# dsub37_to_rj45.net
KiCad netlist of a schematic drawn in EAGLE
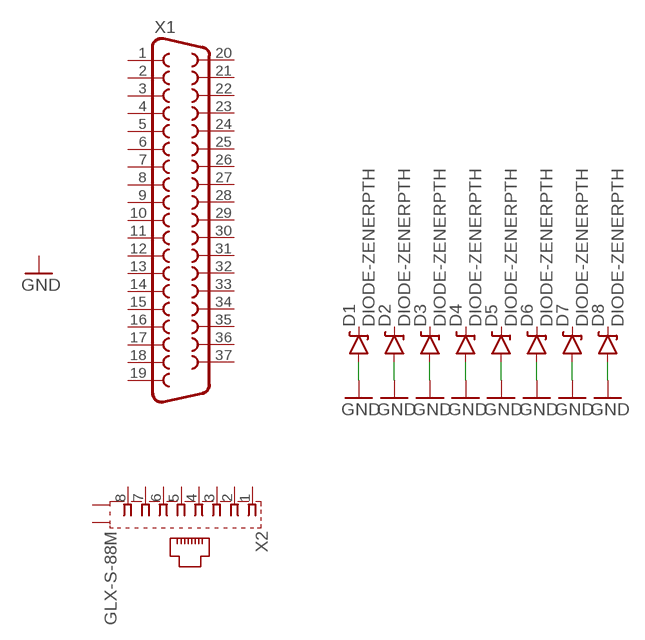
[diagram p0: schematic, sheet 1]

(export (version "E")
  (design (tool "Eeschema 10.0.6"))
  (components
    (comp (ref "D1")
      (value "DIODE-ZENERPTH")
      (footprint "eagle-import:DIODE-ZENER")
      (libsource (lib "eagle-import") (part "DIODE-ZENERPTH"))
    )
    (comp (ref "D2")
      (value "DIODE-ZENERPTH")
      (footprint "eagle-import:DIODE-ZENER")
      (libsource (lib "eagle-import") (part "DIODE-ZENERPTH"))
    )
    (comp (ref "D3")
      (value "DIODE-ZENERPTH")
      (footprint "eagle-import:DIODE-ZENER")
      (libsource (lib "eagle-import") (part "DIODE-ZENERPTH"))
    )
    (comp (ref "D4")
      (value "DIODE-ZENERPTH")
      (footprint "eagle-import:DIODE-ZENER")
      (libsource (lib "eagle-import") (part "DIODE-ZENERPTH"))
    )
    (comp (ref "D5")
      (value "DIODE-ZENERPTH")
      (footprint "eagle-import:DIODE-ZENER")
      (libsource (lib "eagle-import") (part "DIODE-ZENERPTH"))
    )
    (comp (ref "D6")
      (value "DIODE-ZENERPTH")
      (footprint "eagle-import:DIODE-ZENER")
      (libsource (lib "eagle-import") (part "DIODE-ZENERPTH"))
    )
    (comp (ref "D7")
      (value "DIODE-ZENERPTH")
      (footprint "eagle-import:DIODE-ZENER")
      (libsource (lib "eagle-import") (part "DIODE-ZENERPTH"))
    )
    (comp (ref "D8")
      (value "DIODE-ZENERPTH")
      (footprint "eagle-import:DIODE-ZENER")
      (libsource (lib "eagle-import") (part "DIODE-ZENERPTH"))
    )
    (comp (ref "X1")
      (value "F37D")
      (footprint "eagle-import:F37D")
      (libsource (lib "eagle-import") (part "F37D"))
    )
    (comp (ref "X2")
      (value "GLX-S-88M")
      (footprint "eagle-import:GLX-S-88M")
      (libsource (lib "eagle-import") (part "GLX-S-88M"))
    )
  )
  (nets
    (net (code "1") (name "GND") (class "Default")
      (node (ref "D1") (pin "P$2") (pinfunction "A_P$2") (pintype "passive"))
      (node (ref "D2") (pin "P$2") (pinfunction "A_P$2") (pintype "passive"))
      (node (ref "D3") (pin "P$2") (pinfunction "A_P$2") (pintype "passive"))
      (node (ref "D4") (pin "P$2") (pinfunction "A_P$2") (pintype "passive"))
      (node (ref "D5") (pin "P$2") (pinfunction "A_P$2") (pintype "passive"))
      (node (ref "D6") (pin "P$2") (pinfunction "A_P$2") (pintype "passive"))
      (node (ref "D7") (pin "P$2") (pinfunction "A_P$2") (pintype "passive"))
      (node (ref "D8") (pin "P$2") (pinfunction "A_P$2") (pintype "passive"))
    )
    (net (code "2") (name "unconnected-(D1-C-PadP$1)") (class "Default")
      (node (ref "D1") (pin "P$1") (pinfunction "C_P$1") (pintype "passive"))
    )
    (net (code "3") (name "unconnected-(D2-C-PadP$1)") (class "Default")
      (node (ref "D2") (pin "P$1") (pinfunction "C_P$1") (pintype "passive"))
    )
    (net (code "4") (name "unconnected-(D3-C-PadP$1)") (class "Default")
      (node (ref "D3") (pin "P$1") (pinfunction "C_P$1") (pintype "passive"))
    )
    (net (code "5") (name "unconnected-(D4-C-PadP$1)") (class "Default")
      (node (ref "D4") (pin "P$1") (pinfunction "C_P$1") (pintype "passive"))
    )
    (net (code "6") (name "unconnected-(D5-C-PadP$1)") (class "Default")
      (node (ref "D5") (pin "P$1") (pinfunction "C_P$1") (pintype "passive"))
    )
    (net (code "7") (name "unconnected-(D6-C-PadP$1)") (class "Default")
      (node (ref "D6") (pin "P$1") (pinfunction "C_P$1") (pintype "passive"))
    )
    (net (code "8") (name "unconnected-(D7-C-PadP$1)") (class "Default")
      (node (ref "D7") (pin "P$1") (pinfunction "C_P$1") (pintype "passive"))
    )
    (net (code "9") (name "unconnected-(D8-C-PadP$1)") (class "Default")
      (node (ref "D8") (pin "P$1") (pinfunction "C_P$1") (pintype "passive"))
    )
    (net (code "10") (name "unconnected-(X1-Pad1)") (class "Default")
      (node (ref "X1") (pin "1") (pinfunction "1_1") (pintype "passive"))
    )
    (net (code "11") (name "unconnected-(X1-Pad2)") (class "Default")
      (node (ref "X1") (pin "2") (pinfunction "2_2") (pintype "passive"))
    )
    (net (code "12") (name "unconnected-(X1-Pad3)") (class "Default")
      (node (ref "X1") (pin "3") (pinfunction "3_3") (pintype "passive"))
    )
    (net (code "13") (name "unconnected-(X1-Pad4)") (class "Default")
      (node (ref "X1") (pin "4") (pinfunction "4_4") (pintype "passive"))
    )
    (net (code "14") (name "unconnected-(X1-Pad5)") (class "Default")
      (node (ref "X1") (pin "5") (pinfunction "5_5") (pintype "passive"))
    )
    (net (code "15") (name "unconnected-(X1-Pad6)") (class "Default")
      (node (ref "X1") (pin "6") (pinfunction "6_6") (pintype "passive"))
    )
    (net (code "16") (name "unconnected-(X1-Pad7)") (class "Default")
      (node (ref "X1") (pin "7") (pinfunction "7_7") (pintype "passive"))
    )
    (net (code "17") (name "unconnected-(X1-Pad8)") (class "Default")
      (node (ref "X1") (pin "8") (pinfunction "8_8") (pintype "passive"))
    )
    (net (code "18") (name "unconnected-(X1-Pad9)") (class "Default")
      (node (ref "X1") (pin "9") (pinfunction "9_9") (pintype "passive"))
    )
    (net (code "19") (name "unconnected-(X1-Pad10)") (class "Default")
      (node (ref "X1") (pin "10") (pinfunction "10_10") (pintype "passive"))
    )
    (net (code "20") (name "unconnected-(X1-Pad11)") (class "Default")
      (node (ref "X1") (pin "11") (pinfunction "11_11") (pintype "passive"))
    )
    (net (code "21") (name "unconnected-(X1-Pad12)") (class "Default")
      (node (ref "X1") (pin "12") (pinfunction "12_12") (pintype "passive"))
    )
    (net (code "22") (name "unconnected-(X1-Pad13)") (class "Default")
      (node (ref "X1") (pin "13") (pinfunction "13_13") (pintype "passive"))
    )
    (net (code "23") (name "unconnected-(X1-Pad14)") (class "Default")
      (node (ref "X1") (pin "14") (pinfunction "14_14") (pintype "passive"))
    )
    (net (code "24") (name "unconnected-(X1-Pad15)") (class "Default")
      (node (ref "X1") (pin "15") (pinfunction "15_15") (pintype "passive"))
    )
    (net (code "25") (name "unconnected-(X1-Pad16)") (class "Default")
      (node (ref "X1") (pin "16") (pinfunction "16_16") (pintype "passive"))
    )
    (net (code "26") (name "unconnected-(X1-Pad17)") (class "Default")
      (node (ref "X1") (pin "17") (pinfunction "17_17") (pintype "passive"))
    )
    (net (code "27") (name "unconnected-(X1-Pad18)") (class "Default")
      (node (ref "X1") (pin "18") (pinfunction "18_18") (pintype "passive"))
    )
    (net (code "28") (name "unconnected-(X1-Pad19)") (class "Default")
      (node (ref "X1") (pin "19") (pinfunction "19_19") (pintype "passive"))
    )
    (net (code "29") (name "unconnected-(X1-Pad20)") (class "Default")
      (node (ref "X1") (pin "20") (pinfunction "20_20") (pintype "passive"))
    )
    (net (code "30") (name "unconnected-(X1-Pad21)") (class "Default")
      (node (ref "X1") (pin "21") (pinfunction "21_21") (pintype "passive"))
    )
    (net (code "31") (name "unconnected-(X1-Pad22)") (class "Default")
      (node (ref "X1") (pin "22") (pinfunction "22_22") (pintype "passive"))
    )
    (net (code "32") (name "unconnected-(X1-Pad23)") (class "Default")
      (node (ref "X1") (pin "23") (pinfunction "23_23") (pintype "passive"))
    )
    (net (code "33") (name "unconnected-(X1-Pad24)") (class "Default")
      (node (ref "X1") (pin "24") (pinfunction "24_24") (pintype "passive"))
    )
    (net (code "34") (name "unconnected-(X1-Pad25)") (class "Default")
      (node (ref "X1") (pin "25") (pinfunction "25_25") (pintype "passive"))
    )
    (net (code "35") (name "unconnected-(X1-Pad26)") (class "Default")
      (node (ref "X1") (pin "26") (pinfunction "26_26") (pintype "passive"))
    )
    (net (code "36") (name "unconnected-(X1-Pad27)") (class "Default")
      (node (ref "X1") (pin "27") (pinfunction "27_27") (pintype "passive"))
    )
    (net (code "37") (name "unconnected-(X1-Pad28)") (class "Default")
      (node (ref "X1") (pin "28") (pinfunction "28_28") (pintype "passive"))
    )
    (net (code "38") (name "unconnected-(X1-Pad29)") (class "Default")
      (node (ref "X1") (pin "29") (pinfunction "29_29") (pintype "passive"))
    )
    (net (code "39") (name "unconnected-(X1-Pad30)") (class "Default")
      (node (ref "X1") (pin "30") (pinfunction "30_30") (pintype "passive"))
    )
    (net (code "40") (name "unconnected-(X1-Pad31)") (class "Default")
      (node (ref "X1") (pin "31") (pinfunction "31_31") (pintype "passive"))
    )
    (net (code "41") (name "unconnected-(X1-Pad32)") (class "Default")
      (node (ref "X1") (pin "32") (pinfunction "32_32") (pintype "passive"))
    )
    (net (code "42") (name "unconnected-(X1-Pad33)") (class "Default")
      (node (ref "X1") (pin "33") (pinfunction "33_33") (pintype "passive"))
    )
    (net (code "43") (name "unconnected-(X1-Pad34)") (class "Default")
      (node (ref "X1") (pin "34") (pinfunction "34_34") (pintype "passive"))
    )
    (net (code "44") (name "unconnected-(X1-Pad35)") (class "Default")
      (node (ref "X1") (pin "35") (pinfunction "35_35") (pintype "passive"))
    )
    (net (code "45") (name "unconnected-(X1-Pad36)") (class "Default")
      (node (ref "X1") (pin "36") (pinfunction "36_36") (pintype "passive"))
    )
    (net (code "46") (name "unconnected-(X1-Pad37)") (class "Default")
      (node (ref "X1") (pin "37") (pinfunction "37_37") (pintype "passive"))
    )
    (net (code "47") (name "unconnected-(X2-Pad1)") (class "Default")
      (node (ref "X2") (pin "1") (pinfunction "1_1") (pintype "passive"))
    )
    (net (code "48") (name "unconnected-(X2-Pad2)") (class "Default")
      (node (ref "X2") (pin "2") (pinfunction "2_2") (pintype "passive"))
    )
    (net (code "49") (name "unconnected-(X2-Pad3)") (class "Default")
      (node (ref "X2") (pin "3") (pinfunction "3_3") (pintype "passive"))
    )
    (net (code "50") (name "unconnected-(X2-Pad4)") (class "Default")
      (node (ref "X2") (pin "4") (pinfunction "4_4") (pintype "passive"))
    )
    (net (code "51") (name "unconnected-(X2-Pad5)") (class "Default")
      (node (ref "X2") (pin "5") (pinfunction "5_5") (pintype "passive"))
    )
    (net (code "52") (name "unconnected-(X2-Pad6)") (class "Default")
      (node (ref "X2") (pin "6") (pinfunction "6_6") (pintype "passive"))
    )
    (net (code "53") (name "unconnected-(X2-Pad7)") (class "Default")
      (node (ref "X2") (pin "7") (pinfunction "7_7") (pintype "passive"))
    )
    (net (code "54") (name "unconnected-(X2-Pad8)") (class "Default")
      (node (ref "X2") (pin "8") (pinfunction "8_8") (pintype "passive"))
    )
    (net (code "55") (name "unconnected-(X2-PadS1)") (class "Default")
      (node (ref "X2") (pin "S1") (pinfunction "S1_S1") (pintype "passive"))
    )
    (net (code "56") (name "unconnected-(X2-PadS2)") (class "Default")
      (node (ref "X2") (pin "S2") (pinfunction "S2_S2") (pintype "passive"))
    )
  )
)
